# Mech_Interface_Starboard_Deployable.net
KiCad netlist of a schematic drawn in Altium Designer
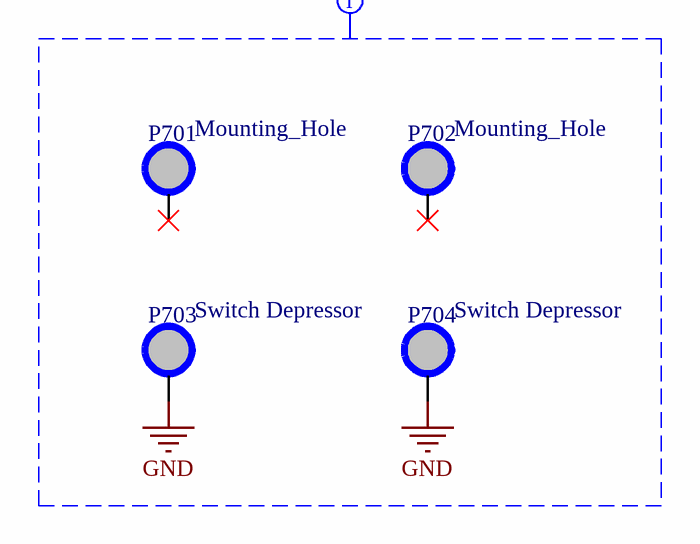
[diagram p0: Mech_Interface_Starboard_Deployable.SchDoc]

(export (version "E")
  (design (tool "Eeschema 10.0.6"))
  (components
    (comp (ref "P701")
      (value "Mounting_Hole")
      (footprint "DepHinge_Mounting_Hole")
      (description "Depolyable Hinge Mounting hole.")
      (fields (field (name "PART NUMBER") "PXX-ABS-00003") (field (name "PUBLISHER") "AlbertaSat"))
      (libsource (lib "Database") (part "Mounting_Hole"))
    )
    (comp (ref "P702")
      (value "Mounting_Hole")
      (footprint "DepHinge_Mounting_Hole")
      (description "Depolyable Hinge Mounting hole.")
      (fields (field (name "PART NUMBER") "PXX-ABS-00003") (field (name "PUBLISHER") "AlbertaSat"))
      (libsource (lib "Database") (part "Mounting_Hole"))
    )
    (comp (ref "P703")
      (value "Switch Depressor")
      (footprint "Switch_Depressor")
      (description "Hardware for depressing the switch")
      (fields
        (field (name "PART NUMBER") "PXX-ABS-00005")
        (field (name "MANUFACTURER PART NUMBER") "Custom")
        (field (name "PUBLISHER") "AlbertaSat")
      )
      (libsource (lib "Database") (part "Mounting_Hole"))
    )
    (comp (ref "P704")
      (value "Switch Depressor")
      (footprint "Switch_Depressor")
      (description "Hardware for depressing the switch")
      (fields
        (field (name "PART NUMBER") "PXX-ABS-00005")
        (field (name "MANUFACTURER PART NUMBER") "Custom")
        (field (name "PUBLISHER") "AlbertaSat")
      )
      (libsource (lib "Database") (part "Mounting_Hole"))
    )
  )
  (nets
    (net (code "1") (name "GND") (class "Default")
      (node (ref "P703") (pin "1") (pinfunction "0_1") (pintype "passive"))
      (node (ref "P704") (pin "1") (pinfunction "0_1") (pintype "passive"))
    )
    (net (code "2") (name "unconnected-(P701-0-Pad1)") (class "Default")
      (node (ref "P701") (pin "1") (pinfunction "0_1") (pintype "passive+no_connect"))
    )
    (net (code "3") (name "unconnected-(P702-0-Pad1)") (class "Default")
      (node (ref "P702") (pin "1") (pinfunction "0_1") (pintype "passive+no_connect"))
    )
  )
)
